# otb-826_breakout_v0_1.net
KiCad netlist of a schematic drawn in EAGLE
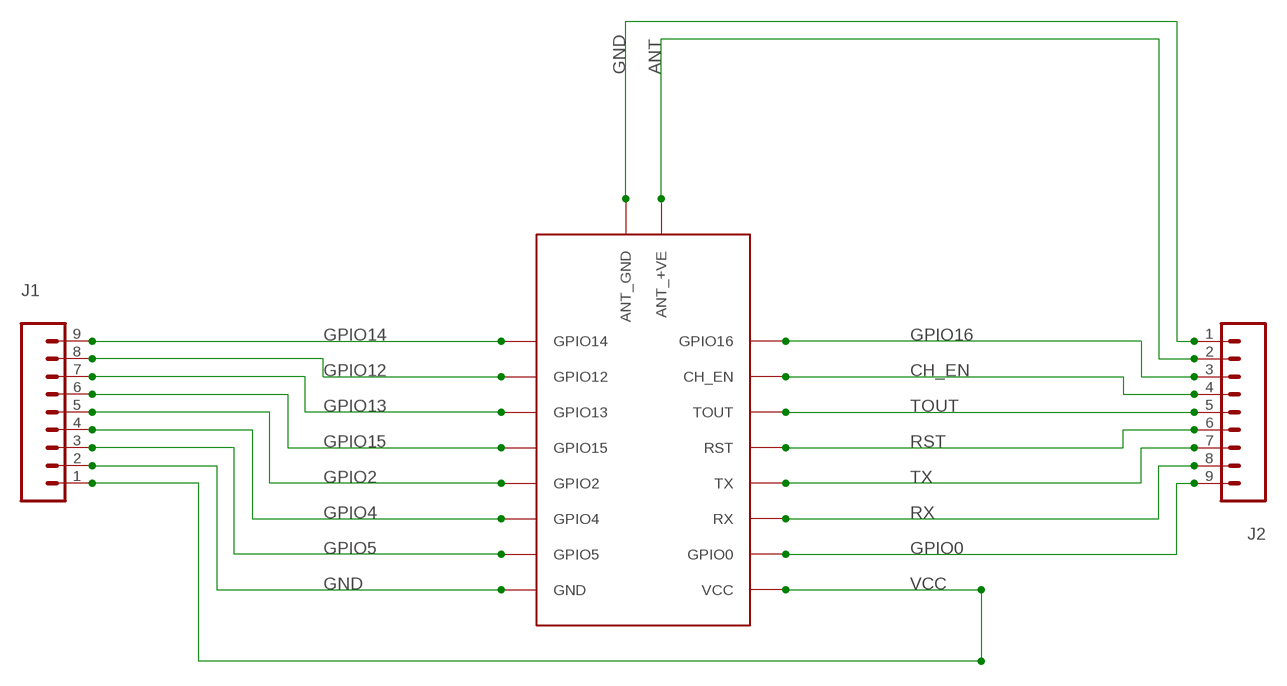
[diagram p0: schematic, sheet 1]

(export (version "E")
  (design (tool "Eeschema 10.0.6"))
  (components
    (comp (ref "J1")
      (value "M09")
      (footprint "eagle-import:1X09")
      (libsource (lib "eagle-import") (part "M09"))
    )
    (comp (ref "J2")
      (value "M09")
      (footprint "eagle-import:1X09")
      (libsource (lib "eagle-import") (part "M09"))
    )
    (comp (ref "OTB-8266")
      (value "OTB-8266-V0.1")
      (footprint "eagle-import:OTB-8266-V0.1")
      (libsource (lib "eagle-import") (part "OTB-8266-V0.1"))
    )
  )
  (nets
    (net (code "1") (name "/ANT") (class "Default")
      (node (ref "J2") (pin "2") (pinfunction "2_2") (pintype "passive"))
      (node (ref "OTB-8266") (pin "ANT_+VE") (pinfunction "ANT_+VE_ANT_+VE") (pintype "bidirectional"))
    )
    (net (code "2") (name "/CH_EN") (class "Default")
      (node (ref "J2") (pin "4") (pinfunction "4_4") (pintype "passive"))
      (node (ref "OTB-8266") (pin "CH_EN") (pinfunction "CH_EN_CH_EN") (pintype "bidirectional"))
    )
    (net (code "3") (name "/GND") (class "Default")
      (node (ref "J1") (pin "2") (pinfunction "2_2") (pintype "passive"))
      (node (ref "J2") (pin "1") (pinfunction "1_1") (pintype "passive"))
      (node (ref "OTB-8266") (pin "ANT_GND") (pinfunction "ANT_GND_ANT_GND") (pintype "bidirectional"))
      (node (ref "OTB-8266") (pin "GND") (pinfunction "GND_GND") (pintype "bidirectional"))
    )
    (net (code "4") (name "/GPIO0") (class "Default")
      (node (ref "J2") (pin "9") (pinfunction "9_9") (pintype "passive"))
      (node (ref "OTB-8266") (pin "GPIO0") (pinfunction "GPIO0_GPIO0") (pintype "bidirectional"))
    )
    (net (code "5") (name "/GPIO2") (class "Default")
      (node (ref "J1") (pin "5") (pinfunction "5_5") (pintype "passive"))
      (node (ref "OTB-8266") (pin "GPIO2") (pinfunction "GPIO2_GPIO2") (pintype "bidirectional"))
    )
    (net (code "6") (name "/GPIO4") (class "Default")
      (node (ref "J1") (pin "4") (pinfunction "4_4") (pintype "passive"))
      (node (ref "OTB-8266") (pin "GPIO4") (pinfunction "GPIO4_GPIO4") (pintype "bidirectional"))
    )
    (net (code "7") (name "/GPIO5") (class "Default")
      (node (ref "J1") (pin "3") (pinfunction "3_3") (pintype "passive"))
      (node (ref "OTB-8266") (pin "GPIO5") (pinfunction "GPIO5_GPIO5") (pintype "bidirectional"))
    )
    (net (code "8") (name "/GPIO12") (class "Default")
      (node (ref "J1") (pin "8") (pinfunction "8_8") (pintype "passive"))
      (node (ref "OTB-8266") (pin "GPIO12") (pinfunction "GPIO12_GPIO12") (pintype "bidirectional"))
    )
    (net (code "9") (name "/GPIO13") (class "Default")
      (node (ref "J1") (pin "7") (pinfunction "7_7") (pintype "passive"))
      (node (ref "OTB-8266") (pin "GPIO13") (pinfunction "GPIO13_GPIO13") (pintype "bidirectional"))
    )
    (net (code "10") (name "/GPIO14") (class "Default")
      (node (ref "J1") (pin "9") (pinfunction "9_9") (pintype "passive"))
      (node (ref "OTB-8266") (pin "GPIO14") (pinfunction "GPIO14_GPIO14") (pintype "bidirectional"))
    )
    (net (code "11") (name "/GPIO15") (class "Default")
      (node (ref "J1") (pin "6") (pinfunction "6_6") (pintype "passive"))
      (node (ref "OTB-8266") (pin "GPIO15") (pinfunction "GPIO15_GPIO15") (pintype "bidirectional"))
    )
    (net (code "12") (name "/GPIO16") (class "Default")
      (node (ref "J2") (pin "3") (pinfunction "3_3") (pintype "passive"))
      (node (ref "OTB-8266") (pin "GPIO16") (pinfunction "GPIO16_GPIO16") (pintype "bidirectional"))
    )
    (net (code "13") (name "/RST") (class "Default")
      (node (ref "J2") (pin "6") (pinfunction "6_6") (pintype "passive"))
      (node (ref "OTB-8266") (pin "RST") (pinfunction "RST_RST") (pintype "bidirectional"))
    )
    (net (code "14") (name "/RX") (class "Default")
      (node (ref "J2") (pin "8") (pinfunction "8_8") (pintype "passive"))
      (node (ref "OTB-8266") (pin "RX") (pinfunction "RX_RX") (pintype "bidirectional"))
    )
    (net (code "15") (name "/TOUT") (class "Default")
      (node (ref "J2") (pin "5") (pinfunction "5_5") (pintype "passive"))
      (node (ref "OTB-8266") (pin "TOUT") (pinfunction "TOUT_TOUT") (pintype "bidirectional"))
    )
    (net (code "16") (name "/TX") (class "Default")
      (node (ref "J2") (pin "7") (pinfunction "7_7") (pintype "passive"))
      (node (ref "OTB-8266") (pin "TX") (pinfunction "TX_TX") (pintype "bidirectional"))
    )
    (net (code "17") (name "/VCC") (class "Default")
      (node (ref "J1") (pin "1") (pinfunction "1_1") (pintype "passive"))
      (node (ref "OTB-8266") (pin "VCC") (pinfunction "VCC_VCC") (pintype "bidirectional"))
    )
  )
)
